# BrewPi_Fuscus_Board_RJ-11.net
KiCad netlist of a schematic drawn in EAGLE
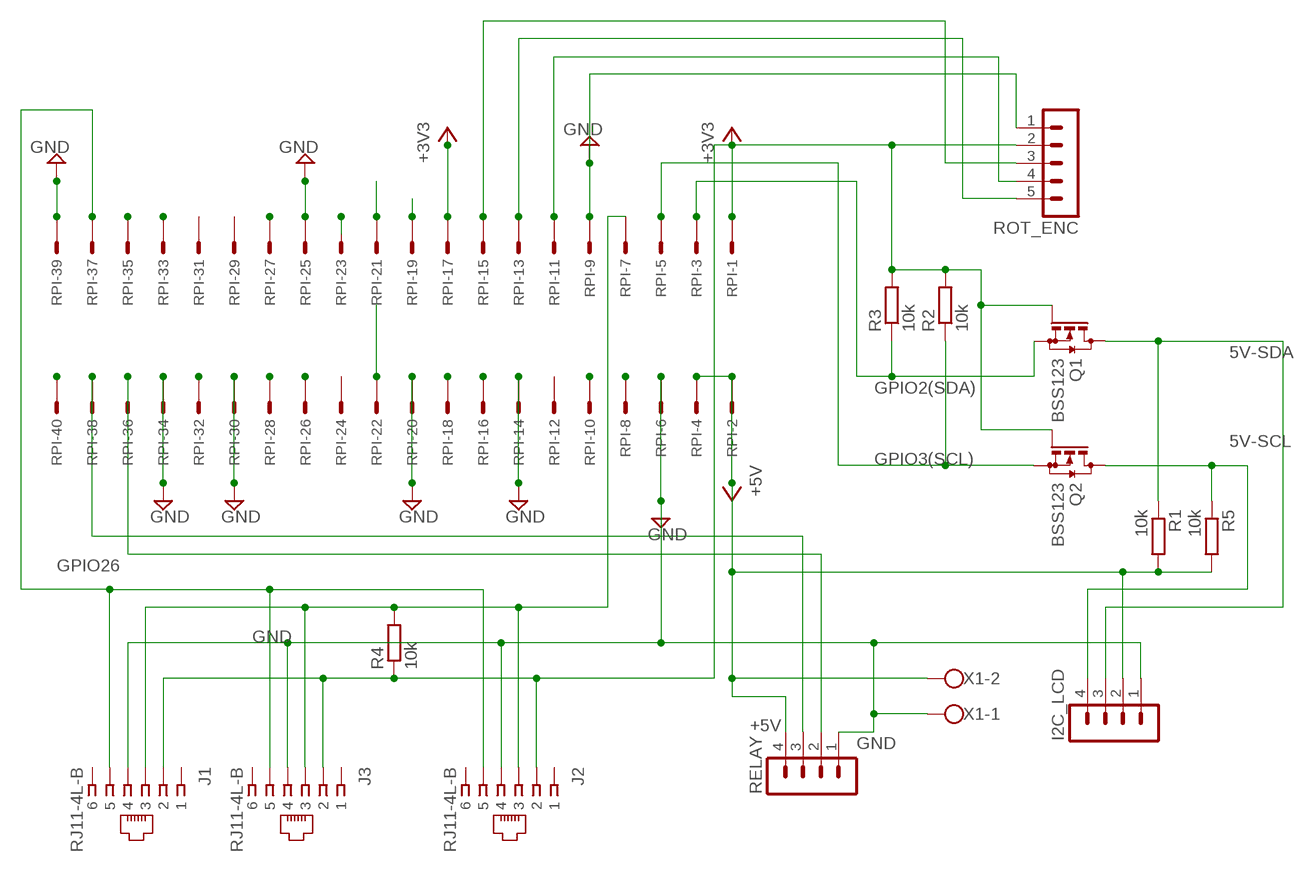
[diagram p0: schematic, sheet 1]

(export (version "E")
  (design (tool "Eeschema 10.0.6"))
  (components
    (comp (ref "I2C_LCD")
      (value "MA04-1")
      (footprint "eagle-import:MA04-1")
      (libsource (lib "eagle-import") (part "MA04-1"))
    )
    (comp (ref "J1")
      (value "RJ11-4L-B")
      (footprint "eagle-import:RJ11-NO_SHIELD")
      (fields (field (name "MF") "TYCO ELECTRONICS"))
      (libsource (lib "eagle-import") (part "RJ11-4L-B"))
    )
    (comp (ref "J2")
      (value "RJ11-4L-B")
      (footprint "eagle-import:RJ11-NO_SHIELD")
      (fields (field (name "MF") "TYCO ELECTRONICS"))
      (libsource (lib "eagle-import") (part "RJ11-4L-B"))
    )
    (comp (ref "J3")
      (value "RJ11-4L-B")
      (footprint "eagle-import:RJ11-NO_SHIELD")
      (fields (field (name "MF") "TYCO ELECTRONICS"))
      (libsource (lib "eagle-import") (part "RJ11-4L-B"))
    )
    (comp (ref "Q1")
      (value "BSS123")
      (footprint "eagle-import:SOT23")
      (libsource (lib "eagle-import") (part "BSS123"))
    )
    (comp (ref "Q2")
      (value "BSS123")
      (footprint "eagle-import:SOT23")
      (libsource (lib "eagle-import") (part "BSS123"))
    )
    (comp (ref "R1")
      (value "10k")
      (footprint "eagle-import:M1206")
      (libsource (lib "eagle-import") (part "R-EU_M1206"))
    )
    (comp (ref "R2")
      (value "10k")
      (footprint "eagle-import:M1206")
      (libsource (lib "eagle-import") (part "R-EU_M1206"))
    )
    (comp (ref "R3")
      (value "10k")
      (footprint "eagle-import:M1206")
      (libsource (lib "eagle-import") (part "R-EU_M1206"))
    )
    (comp (ref "R4")
      (value "10k")
      (footprint "eagle-import:M1206")
      (libsource (lib "eagle-import") (part "R-EU_M1206"))
    )
    (comp (ref "R5")
      (value "10k")
      (footprint "eagle-import:M1206")
      (libsource (lib "eagle-import") (part "R-EU_M1206"))
    )
    (comp (ref "RELAY")
      (value "MA04-1")
      (footprint "eagle-import:MA04-1")
      (libsource (lib "eagle-import") (part "MA04-1"))
    )
    (comp (ref "ROT_ENC")
      (value "MA05-1")
      (footprint "eagle-import:MA05-1")
      (libsource (lib "eagle-import") (part "MA05-1"))
    )
    (comp (ref "RPI")
      (value "057-040-1")
      (footprint "eagle-import:057-040-1")
      (libsource (lib "eagle-import") (part "057-040-1"))
    )
    (comp (ref "X1")
      (value "W237-102")
      (footprint "eagle-import:W237-102")
      (fields (field (name "MPN") "237-102"))
      (libsource (lib "eagle-import") (part "W237-102"))
    )
  )
  (nets
    (net (code "1") (name "+3V3") (class "Default")
      (node (ref "J1") (pin "2") (pinfunction "2_2") (pintype "passive"))
      (node (ref "J2") (pin "2") (pinfunction "2_2") (pintype "passive"))
      (node (ref "J3") (pin "2") (pinfunction "2_2") (pintype "passive"))
      (node (ref "Q1") (pin "1") (pinfunction "G_1") (pintype "passive"))
      (node (ref "Q2") (pin "1") (pinfunction "G_1") (pintype "passive"))
      (node (ref "R2") (pin "2") (pinfunction "2_2") (pintype "passive"))
      (node (ref "R3") (pin "2") (pinfunction "2_2") (pintype "passive"))
      (node (ref "R4") (pin "1") (pinfunction "1_1") (pintype "passive"))
      (node (ref "ROT_ENC") (pin "2") (pinfunction "2_2") (pintype "passive"))
      (node (ref "RPI") (pin "1") (pinfunction "S_1") (pintype "passive"))
      (node (ref "RPI") (pin "17") (pinfunction "S_17") (pintype "passive"))
    )
    (net (code "2") (name "+5V") (class "Default")
      (node (ref "I2C_LCD") (pin "2") (pinfunction "2_2") (pintype "passive"))
      (node (ref "R1") (pin "2") (pinfunction "2_2") (pintype "passive"))
      (node (ref "R5") (pin "2") (pinfunction "2_2") (pintype "passive"))
      (node (ref "RELAY") (pin "4") (pinfunction "4_4") (pintype "passive"))
      (node (ref "RPI") (pin "2") (pinfunction "S_2") (pintype "passive"))
      (node (ref "RPI") (pin "4") (pinfunction "S_4") (pintype "passive"))
      (node (ref "X1") (pin "2") (pinfunction "KL_2") (pintype "passive"))
    )
    (net (code "3") (name "/5V-SCL") (class "Default")
      (node (ref "I2C_LCD") (pin "4") (pinfunction "4_4") (pintype "passive"))
      (node (ref "Q2") (pin "3") (pinfunction "D_3") (pintype "passive"))
      (node (ref "R5") (pin "1") (pinfunction "1_1") (pintype "passive"))
    )
    (net (code "4") (name "/5V-SDA") (class "Default")
      (node (ref "I2C_LCD") (pin "3") (pinfunction "3_3") (pintype "passive"))
      (node (ref "Q1") (pin "3") (pinfunction "D_3") (pintype "passive"))
      (node (ref "R1") (pin "1") (pinfunction "1_1") (pintype "passive"))
    )
    (net (code "5") (name "/GPIO2(SDA)") (class "Default")
      (node (ref "Q1") (pin "2") (pinfunction "S_2") (pintype "passive"))
      (node (ref "R3") (pin "1") (pinfunction "1_1") (pintype "passive"))
      (node (ref "RPI") (pin "3") (pinfunction "S_3") (pintype "passive"))
    )
    (net (code "6") (name "/GPIO3(SCL)") (class "Default")
      (node (ref "Q2") (pin "2") (pinfunction "S_2") (pintype "passive"))
      (node (ref "R2") (pin "1") (pinfunction "1_1") (pintype "passive"))
      (node (ref "RPI") (pin "5") (pinfunction "S_5") (pintype "passive"))
    )
    (net (code "7") (name "/GPIO26") (class "Default")
      (node (ref "J1") (pin "5") (pinfunction "5_5") (pintype "passive"))
      (node (ref "J2") (pin "5") (pinfunction "5_5") (pintype "passive"))
      (node (ref "J3") (pin "5") (pinfunction "5_5") (pintype "passive"))
      (node (ref "RPI") (pin "37") (pinfunction "S_37") (pintype "passive"))
    )
    (net (code "8") (name "GND") (class "Default")
      (node (ref "I2C_LCD") (pin "1") (pinfunction "1_1") (pintype "passive"))
      (node (ref "J1") (pin "4") (pinfunction "4_4") (pintype "passive"))
      (node (ref "J2") (pin "4") (pinfunction "4_4") (pintype "passive"))
      (node (ref "J3") (pin "4") (pinfunction "4_4") (pintype "passive"))
      (node (ref "RELAY") (pin "1") (pinfunction "1_1") (pintype "passive"))
      (node (ref "ROT_ENC") (pin "1") (pinfunction "1_1") (pintype "passive"))
      (node (ref "RPI") (pin "14") (pinfunction "S_14") (pintype "passive"))
      (node (ref "RPI") (pin "20") (pinfunction "S_20") (pintype "passive"))
      (node (ref "RPI") (pin "25") (pinfunction "S_25") (pintype "passive"))
      (node (ref "RPI") (pin "30") (pinfunction "S_30") (pintype "passive"))
      (node (ref "RPI") (pin "34") (pinfunction "S_34") (pintype "passive"))
      (node (ref "RPI") (pin "39") (pinfunction "S_39") (pintype "passive"))
      (node (ref "RPI") (pin "6") (pinfunction "S_6") (pintype "passive"))
      (node (ref "RPI") (pin "9") (pinfunction "S_9") (pintype "passive"))
      (node (ref "X1") (pin "1") (pinfunction "KL_1") (pintype "passive"))
    )
    (net (code "9") (name "Net-(RPIAD-S)") (class "Default")
      (node (ref "RELAY") (pin "2") (pinfunction "2_2") (pintype "passive"))
      (node (ref "RPI") (pin "36") (pinfunction "S_36") (pintype "passive"))
    )
    (net (code "10") (name "Net-(RPIAF-S)") (class "Default")
      (node (ref "RELAY") (pin "3") (pinfunction "3_3") (pintype "passive"))
      (node (ref "RPI") (pin "38") (pinfunction "S_38") (pintype "passive"))
    )
    (net (code "11") (name "Net-(RPIAL-S)") (class "Default")
      (node (ref "J1") (pin "3") (pinfunction "3_3") (pintype "passive"))
      (node (ref "J2") (pin "3") (pinfunction "3_3") (pintype "passive"))
      (node (ref "J3") (pin "3") (pinfunction "3_3") (pintype "passive"))
      (node (ref "R4") (pin "2") (pinfunction "2_2") (pintype "passive"))
      (node (ref "RPI") (pin "7") (pinfunction "S_7") (pintype "passive"))
    )
    (net (code "12") (name "Net-(RPIC-S)") (class "Default")
      (node (ref "ROT_ENC") (pin "4") (pinfunction "4_4") (pintype "passive"))
      (node (ref "RPI") (pin "11") (pinfunction "S_11") (pintype "passive"))
    )
    (net (code "13") (name "Net-(RPIE-S)") (class "Default")
      (node (ref "ROT_ENC") (pin "5") (pinfunction "5_5") (pintype "passive"))
      (node (ref "RPI") (pin "13") (pinfunction "S_13") (pintype "passive"))
    )
    (net (code "14") (name "Net-(RPIG-S)") (class "Default")
      (node (ref "ROT_ENC") (pin "3") (pinfunction "3_3") (pintype "passive"))
      (node (ref "RPI") (pin "15") (pinfunction "S_15") (pintype "passive"))
    )
    (net (code "15") (name "unconnected-(J1-Pad1)") (class "Default")
      (node (ref "J1") (pin "1") (pinfunction "1_1") (pintype "passive"))
    )
    (net (code "16") (name "unconnected-(J1-Pad6)") (class "Default")
      (node (ref "J1") (pin "6") (pinfunction "6_6") (pintype "passive"))
    )
    (net (code "17") (name "unconnected-(J2-Pad1)") (class "Default")
      (node (ref "J2") (pin "1") (pinfunction "1_1") (pintype "passive"))
    )
    (net (code "18") (name "unconnected-(J2-Pad6)") (class "Default")
      (node (ref "J2") (pin "6") (pinfunction "6_6") (pintype "passive"))
    )
    (net (code "19") (name "unconnected-(J3-Pad1)") (class "Default")
      (node (ref "J3") (pin "1") (pinfunction "1_1") (pintype "passive"))
    )
    (net (code "20") (name "unconnected-(J3-Pad6)") (class "Default")
      (node (ref "J3") (pin "6") (pinfunction "6_6") (pintype "passive"))
    )
    (net (code "21") (name "unconnected-(RPIAA-S-Pad33)") (class "Default")
      (node (ref "RPI") (pin "33") (pinfunction "S_33") (pintype "passive"))
    )
    (net (code "22") (name "unconnected-(RPIAC-S-Pad35)") (class "Default")
      (node (ref "RPI") (pin "35") (pinfunction "S_35") (pintype "passive"))
    )
    (net (code "23") (name "unconnected-(RPIAI-S-Pad40)") (class "Default")
      (node (ref "RPI") (pin "40") (pinfunction "S_40") (pintype "passive"))
    )
    (net (code "24") (name "unconnected-(RPIAM-S-Pad8)") (class "Default")
      (node (ref "RPI") (pin "8") (pinfunction "S_8") (pintype "passive"))
    )
    (net (code "25") (name "unconnected-(RPIB-S-Pad10)") (class "Default")
      (node (ref "RPI") (pin "10") (pinfunction "S_10") (pintype "passive"))
    )
    (net (code "26") (name "unconnected-(RPID-S-Pad12)") (class "Default")
      (node (ref "RPI") (pin "12") (pinfunction "S_12") (pintype "passive"))
    )
    (net (code "27") (name "unconnected-(RPIH-S-Pad16)") (class "Default")
      (node (ref "RPI") (pin "16") (pinfunction "S_16") (pintype "passive"))
    )
    (net (code "28") (name "unconnected-(RPIJ-S-Pad18)") (class "Default")
      (node (ref "RPI") (pin "18") (pinfunction "S_18") (pintype "passive"))
    )
    (net (code "29") (name "unconnected-(RPIK-S-Pad19)") (class "Default")
      (node (ref "RPI") (pin "19") (pinfunction "S_19") (pintype "passive"))
    )
    (net (code "30") (name "unconnected-(RPIN-S-Pad21)") (class "Default")
      (node (ref "RPI") (pin "21") (pinfunction "S_21") (pintype "passive"))
    )
    (net (code "31") (name "unconnected-(RPIO-S-Pad22)") (class "Default")
      (node (ref "RPI") (pin "22") (pinfunction "S_22") (pintype "passive"))
    )
    (net (code "32") (name "unconnected-(RPIP-S-Pad23)") (class "Default")
      (node (ref "RPI") (pin "23") (pinfunction "S_23") (pintype "passive"))
    )
    (net (code "33") (name "unconnected-(RPIQ-S-Pad24)") (class "Default")
      (node (ref "RPI") (pin "24") (pinfunction "S_24") (pintype "passive"))
    )
    (net (code "34") (name "unconnected-(RPIS-S-Pad26)") (class "Default")
      (node (ref "RPI") (pin "26") (pinfunction "S_26") (pintype "passive"))
    )
    (net (code "35") (name "unconnected-(RPIT-S-Pad27)") (class "Default")
      (node (ref "RPI") (pin "27") (pinfunction "S_27") (pintype "passive"))
    )
    (net (code "36") (name "unconnected-(RPIU-S-Pad28)") (class "Default")
      (node (ref "RPI") (pin "28") (pinfunction "S_28") (pintype "passive"))
    )
    (net (code "37") (name "unconnected-(RPIV-S-Pad29)") (class "Default")
      (node (ref "RPI") (pin "29") (pinfunction "S_29") (pintype "passive"))
    )
    (net (code "38") (name "unconnected-(RPIY-S-Pad31)") (class "Default")
      (node (ref "RPI") (pin "31") (pinfunction "S_31") (pintype "passive"))
    )
    (net (code "39") (name "unconnected-(RPIZ-S-Pad32)") (class "Default")
      (node (ref "RPI") (pin "32") (pinfunction "S_32") (pintype "passive"))
    )
  )
)
